# 3_waffling80-ALPS_mcu.net
KiCad netlist of a schematic drawn in Altium Designer
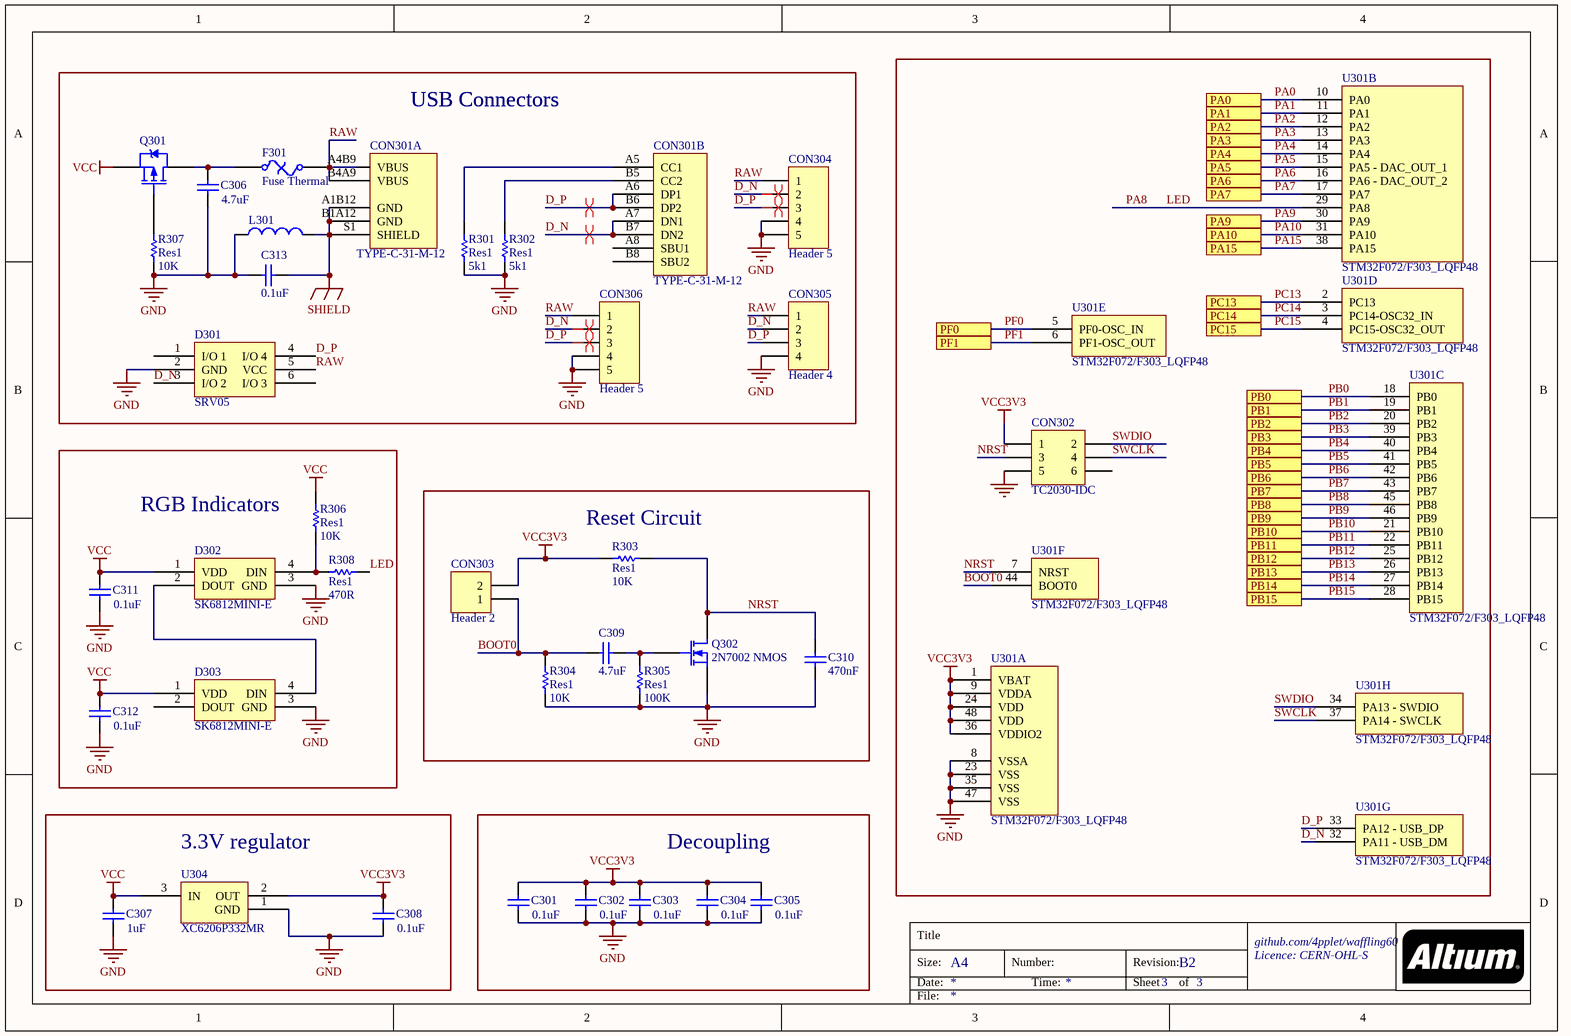
[diagram p0: 3_waffling80-ALPS_mcu.SchDoc]

(export (version "E")
  (design (tool "Eeschema 10.0.6"))
  (components
    (comp (ref "C301")
      (value "0.1uF")
      (footprint "C0603[1608]")
      (description "Capacitor")
      (fields (field (name "LCSC PART #") "C14663") (field (name "MRF.PART") "CC0603KRX7R9BB104"))
      (libsource (lib "Miscellaneous Devices") (part "Cap"))
    )
    (comp (ref "C302")
      (value "0.1uF")
      (footprint "C0603[1608]")
      (description "Capacitor")
      (fields (field (name "LCSC PART #") "C14663") (field (name "MRF.PART") "CC0603KRX7R9BB104"))
      (libsource (lib "Miscellaneous Devices") (part "Cap"))
    )
    (comp (ref "C303")
      (value "0.1uF")
      (footprint "C0603[1608]")
      (description "Capacitor")
      (fields (field (name "LCSC PART #") "C14663") (field (name "MRF.PART") "CC0603KRX7R9BB104"))
      (libsource (lib "Miscellaneous Devices") (part "Cap"))
    )
    (comp (ref "C304")
      (value "0.1uF")
      (footprint "C0603[1608]")
      (description "Capacitor")
      (fields (field (name "LCSC PART #") "C14663") (field (name "MRF.PART") "CC0603KRX7R9BB104"))
      (libsource (lib "Miscellaneous Devices") (part "Cap"))
    )
    (comp (ref "C305")
      (value "0.1uF")
      (footprint "C0603[1608]")
      (description "Capacitor")
      (fields (field (name "LCSC PART #") "C14663") (field (name "MRF.PART") "CC0603KRX7R9BB104"))
      (libsource (lib "Miscellaneous Devices") (part "Cap"))
    )
    (comp (ref "C306")
      (value "4.7uF")
      (footprint "C0603[1608]")
      (description "Capacitor")
      (fields (field (name "LCSC PART #") "C19666") (field (name "MRF.PART") "CL10A475KO8NNNC"))
      (libsource (lib "Miscellaneous Devices") (part "Cap"))
    )
    (comp (ref "C307")
      (value "1uF")
      (footprint "C0603[1608]")
      (description "Capacitor")
      (fields (field (name "LCSC PART #") "C15849") (field (name "MRF.PART") "CL10A105KB8NNNC"))
      (libsource (lib "Miscellaneous Devices") (part "Cap"))
    )
    (comp (ref "C308")
      (value "0.1uF")
      (footprint "C0603[1608]")
      (description "Capacitor")
      (fields (field (name "LCSC PART #") "C14663") (field (name "MRF.PART") "CC0603KRX7R9BB104"))
      (libsource (lib "Miscellaneous Devices") (part "Cap"))
    )
    (comp (ref "C309")
      (value "4.7uF")
      (footprint "C0603[1608]")
      (description "Capacitor")
      (fields (field (name "LCSC PART #") "C19666") (field (name "MRF.PART") "CL10A475KO8NNNC"))
      (libsource (lib "Miscellaneous Devices") (part "Cap"))
    )
    (comp (ref "C310")
      (value "470nF")
      (footprint "C0603[1608]")
      (description "Capacitor")
      (fields (field (name "LCSC PART #") "C1623") (field (name "MRF.PART") "CL10B474KA8NNNC"))
      (libsource (lib "Miscellaneous Devices") (part "Cap"))
    )
    (comp (ref "C311")
      (value "0.1uF")
      (footprint "C0603[1608]")
      (description "Capacitor")
      (fields (field (name "LCSC PART #") "C14663") (field (name "MRF.PART") "CC0603KRX7R9BB104"))
      (libsource (lib "Miscellaneous Devices") (part "Cap"))
    )
    (comp (ref "C312")
      (value "0.1uF")
      (footprint "C0603[1608]")
      (description "Capacitor")
      (fields (field (name "LCSC PART #") "C14663") (field (name "MRF.PART") "CC0603KRX7R9BB104"))
      (libsource (lib "Miscellaneous Devices") (part "Cap"))
    )
    (comp (ref "C313")
      (value "0.1uF")
      (footprint "C0603[1608]")
      (description "Capacitor")
      (fields (field (name "LCSC PART #") "C14663") (field (name "MRF.PART") "CC0603KRX7R9BB104"))
      (libsource (lib "Miscellaneous Devices") (part "Cap"))
    )
    (comp (ref "CON301")
      (value "TYPE-C-31-M-12")
      (footprint "TYPE-C-31-M-12")
      (fields (field (name "LCSC PART #") "C165948"))
      (libsource (lib "Schlib1") (part "TYPE-C-31-M-12"))
    )
    (comp (ref "CON302")
      (value "TC2030-IDC")
      (footprint "TC2030-IDC-NL")
      (description "Header, 3-Pin, Dual row")
      (libsource (lib "Miscellaneous Connectors") (part "Header 3X2"))
    )
    (comp (ref "CON303")
      (value "Header 2")
      (footprint "HDR1X2")
      (description "Header, 2-Pin")
      (libsource (lib "Miscellaneous Connectors") (part "Header 2"))
    )
    (comp (ref "CON304")
      (value "Header 5")
      (footprint "UDB_combo_JST_MOLEX")
      (description "JST for USB daughter board")
      (fields (field (name "LCSC PART #") "C160404") (field (name "MRF.PART") "SM04B-SRSS-TB(LF)(SN)"))
      (libsource (lib "Miscellaneous Connectors") (part "Header 5"))
    )
    (comp (ref "CON305")
      (value "Header 4")
      (footprint "HDR1X4")
      (description "Header, 4-Pin")
      (libsource (lib "Miscellaneous Connectors") (part "Header 4"))
    )
    (comp (ref "CON306")
      (value "Header 5")
      (footprint "Molex 781710004")
      (description "JST for USB daughter board")
      (fields (field (name "LCSC PART #") "C588524") (field (name "MRF.PART") "781710004"))
      (libsource (lib "Miscellaneous Connectors") (part "Header 5"))
    )
    (comp (ref "D301")
      (value "SRV05")
      (footprint "SOT-23-6")
      (fields (field (name "LCSC PART #") "C85364") (field (name "MRF.PART") "SRV05-4-P-T7"))
      (libsource (lib "Keebs") (part "SRV05"))
    )
    (comp (ref "D302")
      (value "SK6812MINI-E")
      (footprint "SK6812MINI-E - shaped")
      (fields (field (name "LCSC PART #") "C524051") (field (name "MRF.PART") "DY-S352818/RGBC/6812-2T"))
      (libsource (lib "Keebs") (part "SK6812MINI-E"))
    )
    (comp (ref "D303")
      (value "SK6812MINI-E")
      (footprint "SK6812MINI-E - shaped")
      (fields (field (name "LCSC PART #") "C524051") (field (name "MRF.PART") "DY-S352818/RGBC/6812-2T"))
      (libsource (lib "Keebs") (part "SK6812MINI-E"))
    )
    (comp (ref "F301")
      (value "Fuse Thermal")
      (footprint "C1206[3216]")
      (description "Thermal Fuse")
      (fields (field (name "LCSC PART #") "C135338") (field (name "MRF.PART") "ASMD1206-050"))
      (libsource (lib "Miscellaneous Devices") (part "Fuse Thermal"))
    )
    (comp (ref "L301")
      (value "Inductor")
      (footprint "L0805")
      (fields (field (name "LCSC PART #") "C1015") (field (name "MRF.PART") "GZ2012D101TF"))
      (libsource (lib "Simulation Generic Components") (part "Inductor"))
    )
    (comp (ref "Q301")
      (value "PMOS-2")
      (footprint "SOT-23-3")
      (description "P-Channel Power MOSFET")
      (fields (field (name "LCSC PART #") "C10487") (field (name "MRF.PART") "SI2301CDS-T1-GE3"))
      (libsource (lib "Miscellaneous Devices") (part "PMOS-2"))
    )
    (comp (ref "Q302")
      (value "2N7002 NMOS")
      (footprint "SOT-23-3")
      (description "N-Channel MOSFET")
      (fields (field (name "LCSC PART #") "C8545") (field (name "MRF.PART") "2N7002"))
      (libsource (lib "Miscellaneous Devices") (part "MOSFET-N"))
    )
    (comp (ref "R301")
      (value "Res1")
      (footprint "R0603[1608]")
      (description "Resistor")
      (fields
        (field (name "ALTIUM_VALUE") "5k1")
        (field (name "LCSC PART #") "C23186")
        (field (name "MRF.PART") "0603WAF5101T5E")
      )
      (libsource (lib "Miscellaneous Devices") (part "Res1"))
    )
    (comp (ref "R302")
      (value "Res1")
      (footprint "R0603[1608]")
      (description "Resistor")
      (fields
        (field (name "ALTIUM_VALUE") "5k1")
        (field (name "LCSC PART #") "C23186")
        (field (name "MRF.PART") "0603WAF5101T5E")
      )
      (libsource (lib "Miscellaneous Devices") (part "Res1"))
    )
    (comp (ref "R303")
      (value "Res1")
      (footprint "R0603[1608]")
      (description "Resistor")
      (fields
        (field (name "ALTIUM_VALUE") "10K")
        (field (name "LCSC PART #") "C25804")
        (field (name "MRF.PART") "0603WAF1002T5E")
      )
      (libsource (lib "Miscellaneous Devices") (part "Res1"))
    )
    (comp (ref "R304")
      (value "Res1")
      (footprint "R0603[1608]")
      (description "Resistor")
      (fields
        (field (name "ALTIUM_VALUE") "10K")
        (field (name "LCSC PART #") "C25804")
        (field (name "MRF.PART") "0603WAF1002T5E")
      )
      (libsource (lib "Miscellaneous Devices") (part "Res1"))
    )
    (comp (ref "R305")
      (value "Res1")
      (footprint "R0603[1608]")
      (description "Resistor")
      (fields
        (field (name "ALTIUM_VALUE") "100K")
        (field (name "LCSC PART #") "C25803")
        (field (name "MRF.PART") "0603WAF1003T5E")
      )
      (libsource (lib "Miscellaneous Devices") (part "Res1"))
    )
    (comp (ref "R306")
      (value "Res1")
      (footprint "R0603[1608]")
      (description "Resistor")
      (fields
        (field (name "ALTIUM_VALUE") "10K")
        (field (name "LCSC PART #") "C25804")
        (field (name "MRF.PART") "0603WAF1002T5E")
      )
      (libsource (lib "Miscellaneous Devices") (part "Res1"))
    )
    (comp (ref "R307")
      (value "Res1")
      (footprint "R0603[1608]")
      (description "Resistor")
      (fields
        (field (name "ALTIUM_VALUE") "10K")
        (field (name "LCSC PART #") "C25804")
        (field (name "MRF.PART") "0603WAF1002T5E")
      )
      (libsource (lib "Miscellaneous Devices") (part "Res1"))
    )
    (comp (ref "R308")
      (value "Res1")
      (footprint "R0603[1608]")
      (description "Resistor")
      (fields
        (field (name "ALTIUM_VALUE") "470R")
        (field (name "LCSC PART #") "C23179")
        (field (name "MRF.PART") "0603WAF4700T5E")
      )
      (libsource (lib "Miscellaneous Devices") (part "Res1"))
    )
    (comp (ref "U301")
      (value "STM32F072/F303_LQFP48")
      (footprint "STM32 - COMBO 7X7MM")
      (fields (field (name "LCSC PART #") "C915660") (field (name "MRF.PART") "APM32F072CBT6"))
      (libsource (lib "Keebs") (part "STM32F072/F303_LQFP48"))
    )
    (comp (ref "U304")
      (value "XC6206P332MR")
      (footprint "SOT-23-3")
      (fields (field (name "LCSC PART #") "C5446"))
      (libsource (lib "Keebs") (part "SOT23 LDO"))
    )
  )
  (nets
    (net (code "1") (name "/BOOT0") (class "Default")
      (node (ref "C309") (pin "1") (pinfunction "1_1") (pintype "passive"))
      (node (ref "CON303") (pin "1") (pinfunction "1_1") (pintype "passive"))
      (node (ref "R304") (pin "1") (pinfunction "1_1") (pintype "passive"))
      (node (ref "U301") (pin "44") (pinfunction "BOOT0_44") (pintype "passive"))
    )
    (net (code "2") (name "/D_N") (class "Default")
      (node (ref "CON301") (pin "A7") (pinfunction "DN1_A7") (pintype "passive"))
      (node (ref "CON301") (pin "B7") (pinfunction "DN2_B7") (pintype "passive"))
      (node (ref "CON304") (pin "2") (pinfunction "2_2") (pintype "passive"))
      (node (ref "CON305") (pin "2") (pinfunction "2_2") (pintype "passive"))
      (node (ref "CON306") (pin "2") (pinfunction "2_2") (pintype "passive"))
      (node (ref "D301") (pin "3") (pinfunction "I/O_2_3") (pintype "passive"))
      (node (ref "U301") (pin "32") (pinfunction "PA11_-_USB_DM_32") (pintype "passive"))
    )
    (net (code "3") (name "/D_P") (class "Default")
      (node (ref "CON301") (pin "A6") (pinfunction "DP1_A6") (pintype "passive"))
      (node (ref "CON301") (pin "B6") (pinfunction "DP2_B6") (pintype "passive"))
      (node (ref "CON304") (pin "3") (pinfunction "3_3") (pintype "passive"))
      (node (ref "CON305") (pin "3") (pinfunction "3_3") (pintype "passive"))
      (node (ref "CON306") (pin "3") (pinfunction "3_3") (pintype "passive"))
      (node (ref "D301") (pin "4") (pinfunction "I/O_4_4") (pintype "passive"))
      (node (ref "U301") (pin "33") (pinfunction "PA12_-_USB_DP_33") (pintype "passive"))
    )
    (net (code "4") (name "/LED") (class "Default")
      (node (ref "R308") (pin "2") (pinfunction "2_2") (pintype "passive"))
      (node (ref "U301") (pin "29") (pinfunction "PA8_29") (pintype "passive"))
    )
    (net (code "5") (name "/NRST") (class "Default")
      (node (ref "C310") (pin "1") (pinfunction "1_1") (pintype "passive"))
      (node (ref "CON302") (pin "3") (pinfunction "3_3") (pintype "passive"))
      (node (ref "Q302") (pin "3") (pinfunction "D_3") (pintype "passive"))
      (node (ref "R303") (pin "2") (pinfunction "2_2") (pintype "passive"))
      (node (ref "U301") (pin "7") (pinfunction "NRST_7") (pintype "passive"))
    )
    (net (code "6") (name "/PA0") (class "Default")
      (node (ref "U301") (pin "10") (pinfunction "PA0_10") (pintype "passive"))
    )
    (net (code "7") (name "/PA1") (class "Default")
      (node (ref "U301") (pin "11") (pinfunction "PA1_11") (pintype "passive"))
    )
    (net (code "8") (name "/PA2") (class "Default")
      (node (ref "U301") (pin "12") (pinfunction "PA2_12") (pintype "passive"))
    )
    (net (code "9") (name "/PA3") (class "Default")
      (node (ref "U301") (pin "13") (pinfunction "PA3_13") (pintype "passive"))
    )
    (net (code "10") (name "/PA4") (class "Default")
      (node (ref "U301") (pin "14") (pinfunction "PA4_14") (pintype "passive"))
    )
    (net (code "11") (name "/PA5") (class "Default")
      (node (ref "U301") (pin "15") (pinfunction "PA5_-_DAC_OUT_1_15") (pintype "passive"))
    )
    (net (code "12") (name "/PA6") (class "Default")
      (node (ref "U301") (pin "16") (pinfunction "PA6_-_DAC_OUT_2_16") (pintype "passive"))
    )
    (net (code "13") (name "/PA7") (class "Default")
      (node (ref "U301") (pin "17") (pinfunction "PA7_17") (pintype "passive"))
    )
    (net (code "14") (name "/PA9") (class "Default")
      (node (ref "U301") (pin "30") (pinfunction "PA9_30") (pintype "passive"))
    )
    (net (code "15") (name "/PA10") (class "Default")
      (node (ref "U301") (pin "31") (pinfunction "PA10_31") (pintype "passive"))
    )
    (net (code "16") (name "/PA15") (class "Default")
      (node (ref "U301") (pin "38") (pinfunction "PA15_38") (pintype "passive"))
    )
    (net (code "17") (name "/PB0") (class "Default")
      (node (ref "U301") (pin "18") (pinfunction "PB0_18") (pintype "passive"))
    )
    (net (code "18") (name "/PB1") (class "Default")
      (node (ref "U301") (pin "19") (pinfunction "PB1_19") (pintype "passive"))
    )
    (net (code "19") (name "/PB2") (class "Default")
      (node (ref "U301") (pin "20") (pinfunction "PB2_20") (pintype "passive"))
    )
    (net (code "20") (name "/PB3") (class "Default")
      (node (ref "U301") (pin "39") (pinfunction "PB3_39") (pintype "passive"))
    )
    (net (code "21") (name "/PB4") (class "Default")
      (node (ref "U301") (pin "40") (pinfunction "PB4_40") (pintype "passive"))
    )
    (net (code "22") (name "/PB5") (class "Default")
      (node (ref "U301") (pin "41") (pinfunction "PB5_41") (pintype "passive"))
    )
    (net (code "23") (name "/PB6") (class "Default")
      (node (ref "U301") (pin "42") (pinfunction "PB6_42") (pintype "passive"))
    )
    (net (code "24") (name "/PB7") (class "Default")
      (node (ref "U301") (pin "43") (pinfunction "PB7_43") (pintype "passive"))
    )
    (net (code "25") (name "/PB8") (class "Default")
      (node (ref "U301") (pin "45") (pinfunction "PB8_45") (pintype "passive"))
    )
    (net (code "26") (name "/PB9") (class "Default")
      (node (ref "U301") (pin "46") (pinfunction "PB9_46") (pintype "passive"))
    )
    (net (code "27") (name "/PB10") (class "Default")
      (node (ref "U301") (pin "21") (pinfunction "PB10_21") (pintype "passive"))
    )
    (net (code "28") (name "/PB11") (class "Default")
      (node (ref "U301") (pin "22") (pinfunction "PB11_22") (pintype "passive"))
    )
    (net (code "29") (name "/PB12") (class "Default")
      (node (ref "U301") (pin "25") (pinfunction "PB12_25") (pintype "passive"))
    )
    (net (code "30") (name "/PB13") (class "Default")
      (node (ref "U301") (pin "26") (pinfunction "PB13_26") (pintype "passive"))
    )
    (net (code "31") (name "/PB14") (class "Default")
      (node (ref "U301") (pin "27") (pinfunction "PB14_27") (pintype "passive"))
    )
    (net (code "32") (name "/PB15") (class "Default")
      (node (ref "U301") (pin "28") (pinfunction "PB15_28") (pintype "passive"))
    )
    (net (code "33") (name "/PC13") (class "Default")
      (node (ref "U301") (pin "2") (pinfunction "PC13_2") (pintype "passive"))
    )
    (net (code "34") (name "/PC14") (class "Default")
      (node (ref "U301") (pin "3") (pinfunction "PC14-OSC32_IN_3") (pintype "passive"))
    )
    (net (code "35") (name "/PC15") (class "Default")
      (node (ref "U301") (pin "4") (pinfunction "PC15-OSC32_OUT_4") (pintype "passive"))
    )
    (net (code "36") (name "/PF0") (class "Default")
      (node (ref "U301") (pin "5") (pinfunction "PF0-OSC_IN_5") (pintype "passive"))
    )
    (net (code "37") (name "/PF1") (class "Default")
      (node (ref "U301") (pin "6") (pinfunction "PF1-OSC_OUT_6") (pintype "passive"))
    )
    (net (code "38") (name "/RAW") (class "Default")
      (node (ref "CON301") (pin "A4B9") (pinfunction "VBUS_A4B9") (pintype "passive"))
      (node (ref "CON301") (pin "B4A9") (pinfunction "VBUS_B4A9") (pintype "passive"))
      (node (ref "CON304") (pin "1") (pinfunction "1_1") (pintype "passive"))
      (node (ref "CON305") (pin "1") (pinfunction "1_1") (pintype "passive"))
      (node (ref "CON306") (pin "1") (pinfunction "1_1") (pintype "passive"))
      (node (ref "D301") (pin "5") (pinfunction "VCC_5") (pintype "passive"))
      (node (ref "F301") (pin "2") (pinfunction "2_2") (pintype "passive"))
    )
    (net (code "39") (name "/SWCLK") (class "Default")
      (node (ref "CON302") (pin "4") (pinfunction "4_4") (pintype "passive"))
      (node (ref "U301") (pin "37") (pinfunction "PA14_-_SWCLK_37") (pintype "passive"))
    )
    (net (code "40") (name "/SWDIO") (class "Default")
      (node (ref "CON302") (pin "2") (pinfunction "2_2") (pintype "passive"))
      (node (ref "U301") (pin "34") (pinfunction "PA13_-_SWDIO_34") (pintype "passive"))
    )
    (net (code "41") (name "GND") (class "Default")
      (node (ref "C301") (pin "1") (pinfunction "1_1") (pintype "passive"))
      (node (ref "C302") (pin "1") (pinfunction "1_1") (pintype "passive"))
      (node (ref "C303") (pin "1") (pinfunction "1_1") (pintype "passive"))
      (node (ref "C304") (pin "1") (pinfunction "1_1") (pintype "passive"))
      (node (ref "C305") (pin "1") (pinfunction "1_1") (pintype "passive"))
      (node (ref "C306") (pin "1") (pinfunction "1_1") (pintype "passive"))
      (node (ref "C307") (pin "1") (pinfunction "1_1") (pintype "passive"))
      (node (ref "C308") (pin "1") (pinfunction "1_1") (pintype "passive"))
      (node (ref "C310") (pin "2") (pinfunction "2_2") (pintype "passive"))
      (node (ref "C311") (pin "1") (pinfunction "1_1") (pintype "passive"))
      (node (ref "C312") (pin "1") (pinfunction "1_1") (pintype "passive"))
      (node (ref "C313") (pin "1") (pinfunction "1_1") (pintype "passive"))
      (node (ref "CON302") (pin "5") (pinfunction "5_5") (pintype "passive"))
      (node (ref "CON304") (pin "4") (pinfunction "4_4") (pintype "passive"))
      (node (ref "CON304") (pin "5") (pinfunction "5_5") (pintype "passive"))
      (node (ref "CON305") (pin "4") (pinfunction "4_4") (pintype "passive"))
      (node (ref "CON306") (pin "4") (pinfunction "4_4") (pintype "passive"))
      (node (ref "CON306") (pin "5") (pinfunction "5_5") (pintype "passive"))
      (node (ref "D301") (pin "2") (pinfunction "GND_2") (pintype "passive"))
      (node (ref "D302") (pin "3") (pinfunction "GND_3") (pintype "passive"))
      (node (ref "D303") (pin "3") (pinfunction "GND_3") (pintype "passive"))
      (node (ref "L301") (pin "1") (pinfunction "1_1") (pintype "passive"))
      (node (ref "Q302") (pin "2") (pinfunction "S_2") (pintype "passive"))
      (node (ref "R301") (pin "2") (pinfunction "2_2") (pintype "passive"))
      (node (ref "R302") (pin "2") (pinfunction "2_2") (pintype "passive"))
      (node (ref "R304") (pin "2") (pinfunction "2_2") (pintype "passive"))
      (node (ref "R305") (pin "2") (pinfunction "2_2") (pintype "passive"))
      (node (ref "R307") (pin "2") (pinfunction "2_2") (pintype "passive"))
      (node (ref "U301") (pin "23") (pinfunction "VSS_23") (pintype "passive"))
      (node (ref "U301") (pin "35") (pinfunction "VSS_35") (pintype "passive"))
      (node (ref "U301") (pin "47") (pinfunction "VSS_47") (pintype "passive"))
      (node (ref "U301") (pin "8") (pinfunction "VSSA_8") (pintype "passive"))
      (node (ref "U304") (pin "1") (pinfunction "GND_1") (pintype "passive"))
    )
    (net (code "42") (name "Net-(CON301B-CC1)") (class "Default")
      (node (ref "CON301") (pin "A5") (pinfunction "CC1_A5") (pintype "passive"))
      (node (ref "R301") (pin "1") (pinfunction "1_1") (pintype "passive"))
    )
    (net (code "43") (name "Net-(CON301B-CC2)") (class "Default")
      (node (ref "CON301") (pin "B5") (pinfunction "CC2_B5") (pintype "passive"))
      (node (ref "R302") (pin "1") (pinfunction "1_1") (pintype "passive"))
    )
    (net (code "44") (name "Net-(D302-DIN)") (class "Default")
      (node (ref "D302") (pin "4") (pinfunction "DIN_4") (pintype "passive"))
      (node (ref "R306") (pin "2") (pinfunction "2_2") (pintype "passive"))
      (node (ref "R308") (pin "1") (pinfunction "1_1") (pintype "passive"))
    )
    (net (code "45") (name "Net-(D302-DOUT)") (class "Default")
      (node (ref "D302") (pin "2") (pinfunction "DOUT_2") (pintype "passive"))
      (node (ref "D303") (pin "4") (pinfunction "DIN_4") (pintype "passive"))
    )
    (net (code "46") (name "Net-(Q301-D)") (class "Default")
      (node (ref "C306") (pin "2") (pinfunction "2_2") (pintype "passive"))
      (node (ref "F301") (pin "1") (pinfunction "1_1") (pintype "passive"))
      (node (ref "Q301") (pin "3") (pinfunction "D_3") (pintype "passive"))
    )
    (net (code "47") (name "Net-(Q301-G)") (class "Default")
      (node (ref "Q301") (pin "1") (pinfunction "G_1") (pintype "passive"))
      (node (ref "R307") (pin "1") (pinfunction "1_1") (pintype "passive"))
    )
    (net (code "48") (name "Net-(Q302-G)") (class "Default")
      (node (ref "C309") (pin "2") (pinfunction "2_2") (pintype "passive"))
      (node (ref "Q302") (pin "1") (pinfunction "G_1") (pintype "passive"))
      (node (ref "R305") (pin "1") (pinfunction "1_1") (pintype "passive"))
    )
    (net (code "49") (name "SHIELD") (class "Default")
      (node (ref "C313") (pin "2") (pinfunction "2_2") (pintype "passive"))
      (node (ref "CON301") (pin "A1B12") (pinfunction "GND_A1B12") (pintype "passive"))
      (node (ref "CON301") (pin "B1A12") (pinfunction "GND_B1A12") (pintype "passive"))
      (node (ref "CON301") (pin "S1") (pinfunction "SHIELD_S1") (pintype "passive"))
      (node (ref "L301") (pin "2") (pinfunction "2_2") (pintype "passive"))
    )
    (net (code "50") (name "VCC") (class "Default")
      (node (ref "C307") (pin "2") (pinfunction "2_2") (pintype "passive"))
      (node (ref "C311") (pin "2") (pinfunction "2_2") (pintype "passive"))
      (node (ref "C312") (pin "2") (pinfunction "2_2") (pintype "passive"))
      (node (ref "D302") (pin "1") (pinfunction "VDD_1") (pintype "passive"))
      (node (ref "D303") (pin "1") (pinfunction "VDD_1") (pintype "passive"))
      (node (ref "Q301") (pin "2") (pinfunction "S_2") (pintype "passive"))
      (node (ref "R306") (pin "1") (pinfunction "1_1") (pintype "passive"))
      (node (ref "U304") (pin "3") (pinfunction "IN_3") (pintype "passive"))
    )
    (net (code "51") (name "VCC3V3") (class "Default")
      (node (ref "C301") (pin "2") (pinfunction "2_2") (pintype "passive"))
      (node (ref "C302") (pin "2") (pinfunction "2_2") (pintype "passive"))
      (node (ref "C303") (pin "2") (pinfunction "2_2") (pintype "passive"))
      (node (ref "C304") (pin "2") (pinfunction "2_2") (pintype "passive"))
      (node (ref "C305") (pin "2") (pinfunction "2_2") (pintype "passive"))
      (node (ref "C308") (pin "2") (pinfunction "2_2") (pintype "passive"))
      (node (ref "CON302") (pin "1") (pinfunction "1_1") (pintype "passive"))
      (node (ref "CON303") (pin "2") (pinfunction "2_2") (pintype "passive"))
      (node (ref "R303") (pin "1") (pinfunction "1_1") (pintype "passive"))
      (node (ref "U301") (pin "1") (pinfunction "VBAT_1") (pintype "passive"))
      (node (ref "U301") (pin "24") (pinfunction "VDD_24") (pintype "passive"))
      (node (ref "U301") (pin "36") (pinfunction "VDDIO2_36") (pintype "passive"))
      (node (ref "U301") (pin "48") (pinfunction "VDD_48") (pintype "passive"))
      (node (ref "U301") (pin "9") (pinfunction "VDDA_9") (pintype "passive"))
      (node (ref "U304") (pin "2") (pinfunction "OUT_2") (pintype "passive"))
    )
    (net (code "52") (name "unconnected-(CON301B-SBU1-PadA8)") (class "Default")
      (node (ref "CON301") (pin "A8") (pinfunction "SBU1_A8") (pintype "passive"))
    )
    (net (code "53") (name "unconnected-(CON301B-SBU2-PadB8)") (class "Default")
      (node (ref "CON301") (pin "B8") (pinfunction "SBU2_B8") (pintype "passive"))
    )
    (net (code "54") (name "unconnected-(CON302-Pad6)") (class "Default")
      (node (ref "CON302") (pin "6") (pinfunction "6_6") (pintype "passive"))
    )
    (net (code "55") (name "unconnected-(D301-I{slash}O_1-Pad1)") (class "Default")
      (node (ref "D301") (pin "1") (pinfunction "I/O_1_1") (pintype "passive"))
    )
    (net (code "56") (name "unconnected-(D301-I{slash}O_3-Pad6)") (class "Default")
      (node (ref "D301") (pin "6") (pinfunction "I/O_3_6") (pintype "passive"))
    )
    (net (code "57") (name "unconnected-(D303-DOUT-Pad2)") (class "Default")
      (node (ref "D303") (pin "2") (pinfunction "DOUT_2") (pintype "passive"))
    )
  )
)
